# LT_ABID_SCR.net
KiCad netlist of a schematic drawn in EAGLE
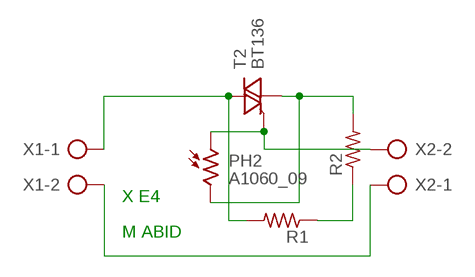
[diagram p0: schematic, sheet 1]

(export (version "E")
  (design (tool "Eeschema 10.0.6"))
  (components
    (comp (ref "PH2")
      (value "A1060_09")
      (footprint "eagle-import:T0-46-A10XX")
      (libsource (lib "eagle-import") (part "A1060_09"))
    )
    (comp (ref "R1")
      (value "R-US_0204/7")
      (footprint "eagle-import:0204_7")
      (libsource (lib "eagle-import") (part "R-US_0204/7"))
    )
    (comp (ref "R2")
      (value "R-US_0204/7")
      (footprint "eagle-import:0204_7")
      (libsource (lib "eagle-import") (part "R-US_0204/7"))
    )
    (comp (ref "T2")
      (value "BT136")
      (footprint "eagle-import:TO220AB")
      (libsource (lib "eagle-import") (part "BT136"))
    )
    (comp (ref "X1")
      (value "AK300/2")
      (footprint "eagle-import:AK300_2")
      (libsource (lib "eagle-import") (part "AK300/2"))
    )
    (comp (ref "X2")
      (value "AK300/2")
      (footprint "eagle-import:AK300_2")
      (libsource (lib "eagle-import") (part "AK300/2"))
    )
  )
  (nets
    (net (code "1") (name "Net-(R1-Pad1)") (class "Default")
      (node (ref "R1") (pin "1") (pinfunction "1_1") (pintype "passive"))
      (node (ref "R2") (pin "1") (pinfunction "1_1") (pintype "passive"))
    )
    (net (code "2") (name "Net-(T2-A1)") (class "Default")
      (node (ref "PH2") (pin "2") (pinfunction "2_2") (pintype "passive"))
      (node (ref "R2") (pin "2") (pinfunction "2_2") (pintype "passive"))
      (node (ref "T2") (pin "1") (pinfunction "A1_1") (pintype "passive"))
    )
    (net (code "3") (name "Net-(T2-A2)") (class "Default")
      (node (ref "R1") (pin "2") (pinfunction "2_2") (pintype "passive"))
      (node (ref "T2") (pin "2") (pinfunction "A2_2") (pintype "passive"))
      (node (ref "X1") (pin "1") (pinfunction "KL_1") (pintype "passive"))
    )
    (net (code "4") (name "Net-(T2-G)") (class "Default")
      (node (ref "PH2") (pin "1") (pinfunction "1_1") (pintype "passive"))
      (node (ref "T2") (pin "3") (pinfunction "G_3") (pintype "passive"))
      (node (ref "X2") (pin "2") (pinfunction "KL_2") (pintype "passive"))
    )
    (net (code "5") (name "Net-(X1B-KL)") (class "Default")
      (node (ref "X1") (pin "2") (pinfunction "KL_2") (pintype "passive"))
      (node (ref "X2") (pin "1") (pinfunction "KL_1") (pintype "passive"))
    )
  )
)
